# regulators.net
KiCad netlist of a schematic drawn in Altium Designer
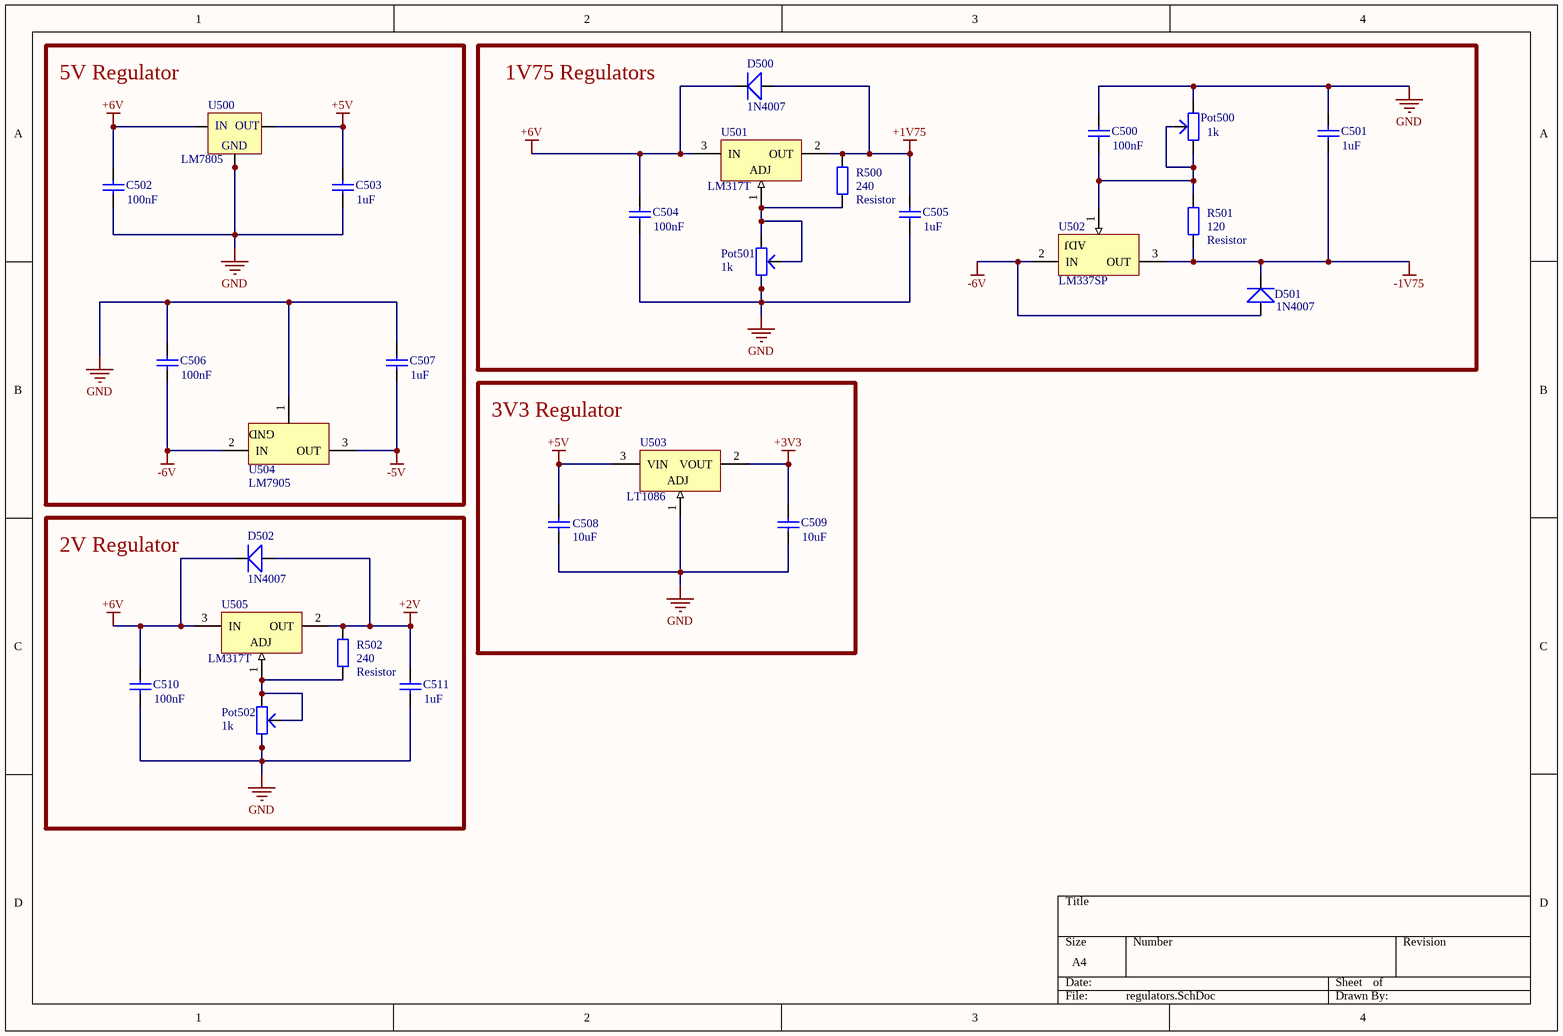
[diagram p0: regulators.SchDoc]

(export (version "E")
  (design (tool "Eeschema 10.0.6"))
  (components
    (comp (ref "C500")
      (value "100nF")
      (footprint "Cap-1")
      (fields (field (name "Comment") "Cap"))
      (libsource (lib "AAURacing") (part "Capacitor 1 space"))
    )
    (comp (ref "C501")
      (value "1uF")
      (footprint "Cap-1")
      (fields (field (name "Comment") "Cap"))
      (libsource (lib "AAURacing") (part "Capacitor 1 space"))
    )
    (comp (ref "C502")
      (value "100nF")
      (footprint "Cap-1")
      (fields (field (name "Comment") "Cap"))
      (libsource (lib "AAURacing") (part "Capacitor 1 space"))
    )
    (comp (ref "C503")
      (value "1uF")
      (footprint "Cap-1")
      (fields (field (name "Comment") "Cap"))
      (libsource (lib "AAURacing") (part "Capacitor 1 space"))
    )
    (comp (ref "C504")
      (value "100nF")
      (footprint "Cap-1")
      (fields (field (name "Comment") "Cap"))
      (libsource (lib "AAURacing") (part "Capacitor 1 space"))
    )
    (comp (ref "C505")
      (value "1uF")
      (footprint "Cap-1")
      (fields (field (name "Comment") "Cap"))
      (libsource (lib "AAURacing") (part "Capacitor 1 space"))
    )
    (comp (ref "C506")
      (value "100nF")
      (footprint "Cap-1")
      (fields (field (name "Comment") "Cap"))
      (libsource (lib "AAURacing") (part "Capacitor 1 space"))
    )
    (comp (ref "C507")
      (value "1uF")
      (footprint "Cap-1")
      (fields (field (name "Comment") "Cap"))
      (libsource (lib "AAURacing") (part "Capacitor 1 space"))
    )
    (comp (ref "C508")
      (value "10uF")
      (footprint "Cap-1")
      (fields (field (name "Comment") "Cap"))
      (libsource (lib "AAURacing") (part "Capacitor 1 space"))
    )
    (comp (ref "C509")
      (value "10uF")
      (footprint "Cap-1")
      (fields (field (name "Comment") "Cap"))
      (libsource (lib "AAURacing") (part "Capacitor 1 space"))
    )
    (comp (ref "C510")
      (value "100nF")
      (footprint "Cap-1")
      (fields (field (name "Comment") "Cap"))
      (libsource (lib "AAURacing") (part "Capacitor 1 space"))
    )
    (comp (ref "C511")
      (value "1uF")
      (footprint "Cap-1")
      (fields (field (name "Comment") "Cap"))
      (libsource (lib "AAURacing") (part "Capacitor 1 space"))
    )
    (comp (ref "D500")
      (value "1N4007")
      (footprint "1N4007")
      (libsource (lib "mit_seje_library") (part "1N4007"))
    )
    (comp (ref "D501")
      (value "1N4007")
      (footprint "1N4007")
      (libsource (lib "mit_seje_library") (part "1N4007"))
    )
    (comp (ref "D502")
      (value "1N4007")
      (footprint "1N4007")
      (libsource (lib "mit_seje_library") (part "1N4007"))
    )
    (comp (ref "Pot500")
      (value "1k")
      (footprint "Pot trim slim high")
      (description "Potentiometer")
      (fields (field (name "Comment") "Pot Trim"))
      (libsource (lib "AAURacing") (part "Pot Trim"))
    )
    (comp (ref "Pot501")
      (value "1k")
      (footprint "Pot trim slim high")
      (description "Potentiometer")
      (fields (field (name "Comment") "Pot Trim"))
      (libsource (lib "AAURacing") (part "Pot Trim"))
    )
    (comp (ref "Pot502")
      (value "1k")
      (footprint "Pot trim slim high")
      (description "Potentiometer")
      (fields (field (name "Comment") "Pot Trim"))
      (libsource (lib "AAURacing") (part "Pot Trim"))
    )
    (comp (ref "R500")
      (value "Resistor")
      (footprint "RES THT 9mm")
      (fields (field (name "ALTIUM_VALUE") "240"))
      (libsource (lib "AAURacing") (part "Resistor"))
    )
    (comp (ref "R501")
      (value "Resistor")
      (footprint "RES THT 9mm")
      (fields (field (name "ALTIUM_VALUE") "120"))
      (libsource (lib "AAURacing") (part "Resistor"))
    )
    (comp (ref "R502")
      (value "Resistor")
      (footprint "RES THT 9mm")
      (fields (field (name "ALTIUM_VALUE") "240"))
      (libsource (lib "AAURacing") (part "Resistor"))
    )
    (comp (ref "U500")
      (value "LM7805")
      (footprint "TO-220")
      (libsource (lib "AAURacing") (part "Voltage Regulator"))
    )
    (comp (ref "U501")
      (value "LM317T")
      (footprint "TO-220")
      (description "1.5A, 1.2V to 37V Adjustable Voltage Regulator, 3-Pin TO-220")
      (libsource (lib "Altium Content Vault") (part "PM-REG-117-SIL3"))
    )
    (comp (ref "U502")
      (value "LM337SP")
      (footprint "TO220")
      (description "Three-Terminal Negative Voltage Regulator, 3-Pin TO-220")
      (libsource (lib "Altium Content Vault") (part "PM-REG-117-CY3"))
    )
    (comp (ref "U503")
      (value "LT1086")
      (footprint "LT-T-3")
      (fields (field (name "MANUFACTURER") "Linear Technology") (field (name "PARTNUMBER") "LT1086CT#PBF"))
      (libsource (lib "Altium Content Vault") (part "LT-LT1XXXX"))
    )
    (comp (ref "U504")
      (value "LM7905")
      (footprint "NDE0003A")
      (description "3-Terminal Negative Regulator, 3-pin TO-220, Pb-Free")
      (fields (field (name "MANUFACTURER") "Texas Instruments"))
      (libsource (lib "Altium Content Vault") (part "PM-REG-LM7905-SIL3"))
    )
    (comp (ref "U505")
      (value "LM317T")
      (footprint "TO-220")
      (description "1.5A, 1.2V to 37V Adjustable Voltage Regulator, 3-Pin TO-220")
      (libsource (lib "Altium Content Vault") (part "PM-REG-117-SIL3"))
    )
  )
  (nets
    (net (code "1") (name "+1V75") (class "Default")
      (node (ref "C505") (pin "2") (pinfunction "g_2") (pintype "passive"))
      (node (ref "D500") (pin "1") (pinfunction "1_1") (pintype "passive"))
      (node (ref "R500") (pin "2") (pinfunction "2_2") (pintype "passive"))
      (node (ref "U501") (pin "2") (pinfunction "OUT_2") (pintype "power_in"))
    )
    (net (code "2") (name "+2V") (class "Default")
      (node (ref "C511") (pin "2") (pinfunction "g_2") (pintype "passive"))
      (node (ref "D502") (pin "1") (pinfunction "1_1") (pintype "passive"))
      (node (ref "R502") (pin "2") (pinfunction "2_2") (pintype "passive"))
      (node (ref "U505") (pin "2") (pinfunction "OUT_2") (pintype "power_in"))
    )
    (net (code "3") (name "+3V3") (class "Default")
      (node (ref "C509") (pin "2") (pinfunction "g_2") (pintype "passive"))
      (node (ref "U503") (pin "2") (pinfunction "VOUT_2") (pintype "power_in"))
    )
    (net (code "4") (name "+5V") (class "Default")
      (node (ref "C503") (pin "2") (pinfunction "g_2") (pintype "passive"))
      (node (ref "C508") (pin "2") (pinfunction "g_2") (pintype "passive"))
      (node (ref "U500") (pin "3") (pinfunction "OUT_3") (pintype "passive"))
      (node (ref "U503") (pin "3") (pinfunction "VIN_3") (pintype "power_in"))
    )
    (net (code "5") (name "+6V") (class "Default")
      (node (ref "C502") (pin "2") (pinfunction "g_2") (pintype "passive"))
      (node (ref "C504") (pin "2") (pinfunction "g_2") (pintype "passive"))
      (node (ref "C510") (pin "2") (pinfunction "g_2") (pintype "passive"))
      (node (ref "D500") (pin "2") (pinfunction "2_2") (pintype "passive"))
      (node (ref "D502") (pin "2") (pinfunction "2_2") (pintype "passive"))
      (node (ref "U500") (pin "1") (pinfunction "IN_1") (pintype "passive"))
      (node (ref "U501") (pin "3") (pinfunction "IN_3") (pintype "power_in"))
      (node (ref "U505") (pin "3") (pinfunction "IN_3") (pintype "power_in"))
    )
    (net (code "6") (name "-1V75") (class "Default")
      (node (ref "C501") (pin "1") (pinfunction "1_1") (pintype "passive"))
      (node (ref "D501") (pin "2") (pinfunction "2_2") (pintype "passive"))
      (node (ref "R501") (pin "1") (pinfunction "1_1") (pintype "passive"))
      (node (ref "U502") (pin "3") (pinfunction "OUT_3") (pintype "power_in"))
    )
    (net (code "7") (name "-5V") (class "Default")
      (node (ref "C507") (pin "1") (pinfunction "1_1") (pintype "passive"))
      (node (ref "U504") (pin "3") (pinfunction "OUT_3") (pintype "power_in"))
    )
    (net (code "8") (name "-6V") (class "Default")
      (node (ref "C506") (pin "1") (pinfunction "1_1") (pintype "passive"))
      (node (ref "D501") (pin "1") (pinfunction "1_1") (pintype "passive"))
      (node (ref "U502") (pin "2") (pinfunction "IN_2") (pintype "power_in"))
      (node (ref "U504") (pin "2") (pinfunction "IN_2") (pintype "power_in"))
    )
    (net (code "9") (name "GND") (class "Default")
      (node (ref "C500") (pin "2") (pinfunction "g_2") (pintype "passive"))
      (node (ref "C501") (pin "2") (pinfunction "g_2") (pintype "passive"))
      (node (ref "C502") (pin "1") (pinfunction "1_1") (pintype "passive"))
      (node (ref "C503") (pin "1") (pinfunction "1_1") (pintype "passive"))
      (node (ref "C504") (pin "1") (pinfunction "1_1") (pintype "passive"))
      (node (ref "C505") (pin "1") (pinfunction "1_1") (pintype "passive"))
      (node (ref "C506") (pin "2") (pinfunction "g_2") (pintype "passive"))
      (node (ref "C507") (pin "2") (pinfunction "g_2") (pintype "passive"))
      (node (ref "C508") (pin "1") (pinfunction "1_1") (pintype "passive"))
      (node (ref "C509") (pin "1") (pinfunction "1_1") (pintype "passive"))
      (node (ref "C510") (pin "1") (pinfunction "1_1") (pintype "passive"))
      (node (ref "C511") (pin "1") (pinfunction "1_1") (pintype "passive"))
      (node (ref "Pot500") (pin "1") (pinfunction "1_1") (pintype "passive"))
      (node (ref "Pot501") (pin "1") (pinfunction "1_1") (pintype "passive"))
      (node (ref "Pot502") (pin "1") (pinfunction "1_1") (pintype "passive"))
      (node (ref "U500") (pin "2") (pinfunction "GND_2") (pintype "passive"))
      (node (ref "U500") (pin "4") (pinfunction "GND_4") (pintype "passive"))
      (node (ref "U503") (pin "1") (pinfunction "ADJ_1") (pintype "input"))
      (node (ref "U504") (pin "1") (pinfunction "GND_1") (pintype "power_in"))
    )
    (net (code "10") (name "Net-(U501-ADJ)") (class "Default")
      (node (ref "Pot501") (pin "2") (pinfunction "2_2") (pintype "passive"))
      (node (ref "Pot501") (pin "3") (pinfunction "3_3") (pintype "passive"))
      (node (ref "R500") (pin "1") (pinfunction "1_1") (pintype "passive"))
      (node (ref "U501") (pin "1") (pinfunction "ADJ_1") (pintype "input"))
    )
    (net (code "11") (name "Net-(U502-ADJ)") (class "Default")
      (node (ref "C500") (pin "1") (pinfunction "1_1") (pintype "passive"))
      (node (ref "Pot500") (pin "2") (pinfunction "2_2") (pintype "passive"))
      (node (ref "Pot500") (pin "3") (pinfunction "3_3") (pintype "passive"))
      (node (ref "R501") (pin "2") (pinfunction "2_2") (pintype "passive"))
      (node (ref "U502") (pin "1") (pinfunction "ADJ_1") (pintype "input"))
    )
    (net (code "12") (name "Net-(U505-ADJ)") (class "Default")
      (node (ref "Pot502") (pin "2") (pinfunction "2_2") (pintype "passive"))
      (node (ref "Pot502") (pin "3") (pinfunction "3_3") (pintype "passive"))
      (node (ref "R502") (pin "1") (pinfunction "1_1") (pintype "passive"))
      (node (ref "U505") (pin "1") (pinfunction "ADJ_1") (pintype "input"))
    )
  )
)
